# MAG.net
KiCad netlist of a schematic drawn in EAGLE
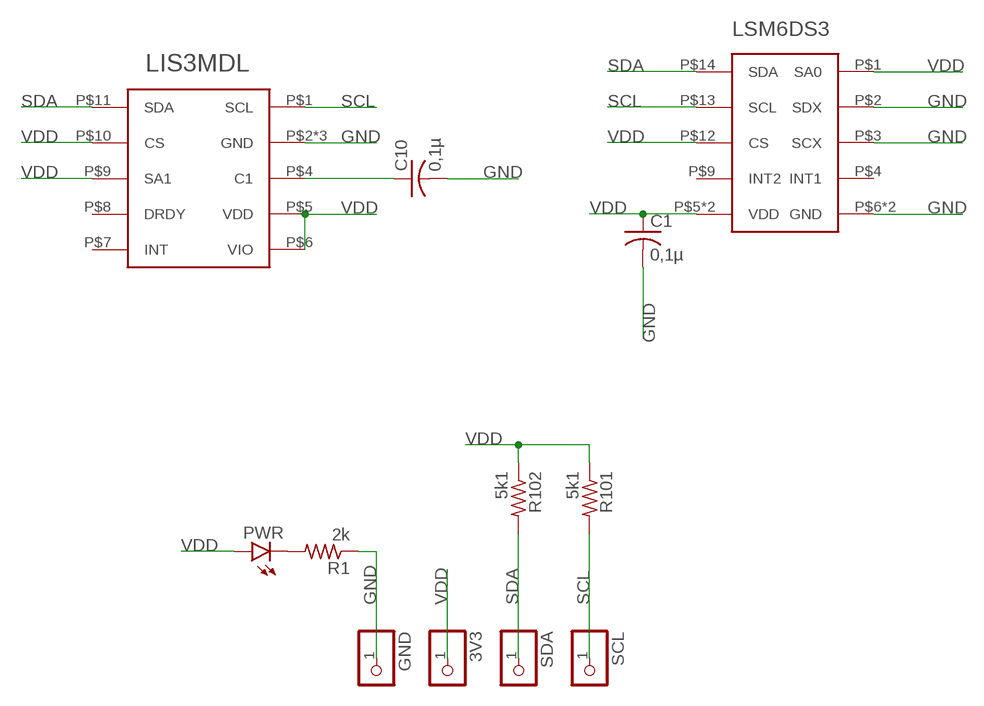
[diagram p0: schematic, sheet 1]

(export (version "E")
  (design (tool "Eeschema 10.0.6"))
  (components
    (comp (ref "3V3")
      (value "PINHD-1X1")
      (footprint "eagle-import:1X01")
      (libsource (lib "eagle-import") (part "PINHD-1X1"))
    )
    (comp (ref "C1")
      (value "0,1µ")
      (footprint "eagle-import:C0603")
      (libsource (lib "eagle-import") (part "C-USC0603"))
    )
    (comp (ref "C10")
      (value "0,1µ")
      (footprint "eagle-import:C0603")
      (libsource (lib "eagle-import") (part "C-USC0603"))
    )
    (comp (ref "GND")
      (value "PINHD-1X1")
      (footprint "eagle-import:1X01")
      (libsource (lib "eagle-import") (part "PINHD-1X1"))
    )
    (comp (ref "LIS3MDL")
      (value "LIS3MDL")
      (footprint "eagle-import:LIS3MDL")
      (libsource (lib "eagle-import") (part "LIS3MDL"))
    )
    (comp (ref "LSM6DS3")
      (value "LSM6DS3")
      (footprint "eagle-import:LSM6DS3")
      (libsource (lib "eagle-import") (part "LSM6DS3"))
    )
    (comp (ref "PWR")
      (value "LEDCHIPLED_0603")
      (footprint "eagle-import:CHIPLED_0603")
      (libsource (lib "eagle-import") (part "LEDCHIPLED_0603"))
    )
    (comp (ref "R1")
      (value "2k")
      (footprint "eagle-import:R0603")
      (libsource (lib "eagle-import") (part "R-US_R0603"))
    )
    (comp (ref "R101")
      (value "5k1")
      (footprint "eagle-import:R0603")
      (libsource (lib "eagle-import") (part "R-US_R0603"))
    )
    (comp (ref "R102")
      (value "5k1")
      (footprint "eagle-import:R0603")
      (libsource (lib "eagle-import") (part "R-US_R0603"))
    )
    (comp (ref "SCL")
      (value "PINHD-1X1")
      (footprint "eagle-import:1X01")
      (libsource (lib "eagle-import") (part "PINHD-1X1"))
    )
    (comp (ref "SDA")
      (value "PINHD-1X1")
      (footprint "eagle-import:1X01")
      (libsource (lib "eagle-import") (part "PINHD-1X1"))
    )
  )
  (nets
    (net (code "1") (name "/GND") (class "Default")
      (node (ref "C1") (pin "2") (pinfunction "2_2") (pintype "passive"))
      (node (ref "C10") (pin "2") (pinfunction "2_2") (pintype "passive"))
      (node (ref "GND") (pin "1") (pinfunction "1_1") (pintype "passive"))
      (node (ref "LIS3MDL") (pin "P$12") (pinfunction "GND_P$12") (pintype "bidirectional"))
      (node (ref "LIS3MDL") (pin "P$2") (pinfunction "GND_P$2") (pintype "bidirectional"))
      (node (ref "LIS3MDL") (pin "P$3") (pinfunction "GND_P$3") (pintype "bidirectional"))
      (node (ref "LSM6DS3") (pin "P$2") (pinfunction "SDX_P$2") (pintype "bidirectional"))
      (node (ref "LSM6DS3") (pin "P$3") (pinfunction "SCX_P$3") (pintype "bidirectional"))
      (node (ref "LSM6DS3") (pin "P$6") (pinfunction "GND_P$6") (pintype "bidirectional"))
      (node (ref "LSM6DS3") (pin "P$7") (pinfunction "GND_P$7") (pintype "bidirectional"))
      (node (ref "R1") (pin "1") (pinfunction "1_1") (pintype "passive"))
    )
    (net (code "2") (name "/SCL") (class "Default")
      (node (ref "LIS3MDL") (pin "P$1") (pinfunction "SCL_P$1") (pintype "bidirectional"))
      (node (ref "LSM6DS3") (pin "P$13") (pinfunction "SCL_P$13") (pintype "bidirectional"))
      (node (ref "R101") (pin "2") (pinfunction "2_2") (pintype "passive"))
      (node (ref "SCL") (pin "1") (pinfunction "1_1") (pintype "passive"))
    )
    (net (code "3") (name "/SDA") (class "Default")
      (node (ref "LIS3MDL") (pin "P$11") (pinfunction "SDA_P$11") (pintype "bidirectional"))
      (node (ref "LSM6DS3") (pin "P$14") (pinfunction "SDA_P$14") (pintype "bidirectional"))
      (node (ref "R102") (pin "2") (pinfunction "2_2") (pintype "passive"))
      (node (ref "SDA") (pin "1") (pinfunction "1_1") (pintype "passive"))
    )
    (net (code "4") (name "/VDD") (class "Default")
      (node (ref "3V3") (pin "1") (pinfunction "1_1") (pintype "passive"))
      (node (ref "C1") (pin "1") (pinfunction "1_1") (pintype "passive"))
      (node (ref "LIS3MDL") (pin "P$10") (pinfunction "CS_P$10") (pintype "bidirectional"))
      (node (ref "LIS3MDL") (pin "P$5") (pinfunction "VDD_P$5") (pintype "bidirectional"))
      (node (ref "LIS3MDL") (pin "P$6") (pinfunction "VIO_P$6") (pintype "bidirectional"))
      (node (ref "LIS3MDL") (pin "P$9") (pinfunction "SA1_P$9") (pintype "bidirectional"))
      (node (ref "LSM6DS3") (pin "P$1") (pinfunction "SA0_P$1") (pintype "bidirectional"))
      (node (ref "LSM6DS3") (pin "P$12") (pinfunction "CS_P$12") (pintype "bidirectional"))
      (node (ref "LSM6DS3") (pin "P$5") (pinfunction "VDD_P$5") (pintype "bidirectional"))
      (node (ref "LSM6DS3") (pin "P$8") (pinfunction "VDD_P$8") (pintype "bidirectional"))
      (node (ref "PWR") (pin "A") (pinfunction "A_A") (pintype "passive"))
      (node (ref "R101") (pin "1") (pinfunction "1_1") (pintype "passive"))
      (node (ref "R102") (pin "1") (pinfunction "1_1") (pintype "passive"))
    )
    (net (code "5") (name "Net-(LIS3MDL-C1)") (class "Default")
      (node (ref "C10") (pin "1") (pinfunction "1_1") (pintype "passive"))
      (node (ref "LIS3MDL") (pin "P$4") (pinfunction "C1_P$4") (pintype "bidirectional"))
    )
    (net (code "6") (name "Net-(PWR-PadC)") (class "Default")
      (node (ref "PWR") (pin "C") (pinfunction "C_C") (pintype "passive"))
      (node (ref "R1") (pin "2") (pinfunction "2_2") (pintype "passive"))
    )
    (net (code "7") (name "unconnected-(LIS3MDL-DRDY-PadP$8)") (class "Default")
      (node (ref "LIS3MDL") (pin "P$8") (pinfunction "DRDY_P$8") (pintype "bidirectional"))
    )
    (net (code "8") (name "unconnected-(LIS3MDL-INT-PadP$7)") (class "Default")
      (node (ref "LIS3MDL") (pin "P$7") (pinfunction "INT_P$7") (pintype "bidirectional"))
    )
    (net (code "9") (name "unconnected-(LSM6DS3-INT1-PadP$4)") (class "Default")
      (node (ref "LSM6DS3") (pin "P$4") (pinfunction "INT1_P$4") (pintype "bidirectional"))
    )
    (net (code "10") (name "unconnected-(LSM6DS3-INT2-PadP$9)") (class "Default")
      (node (ref "LSM6DS3") (pin "P$9") (pinfunction "INT2_P$9") (pintype "bidirectional"))
    )
  )
)
